# Buck_5-12V.net
KiCad netlist of a schematic drawn in Altium Designer
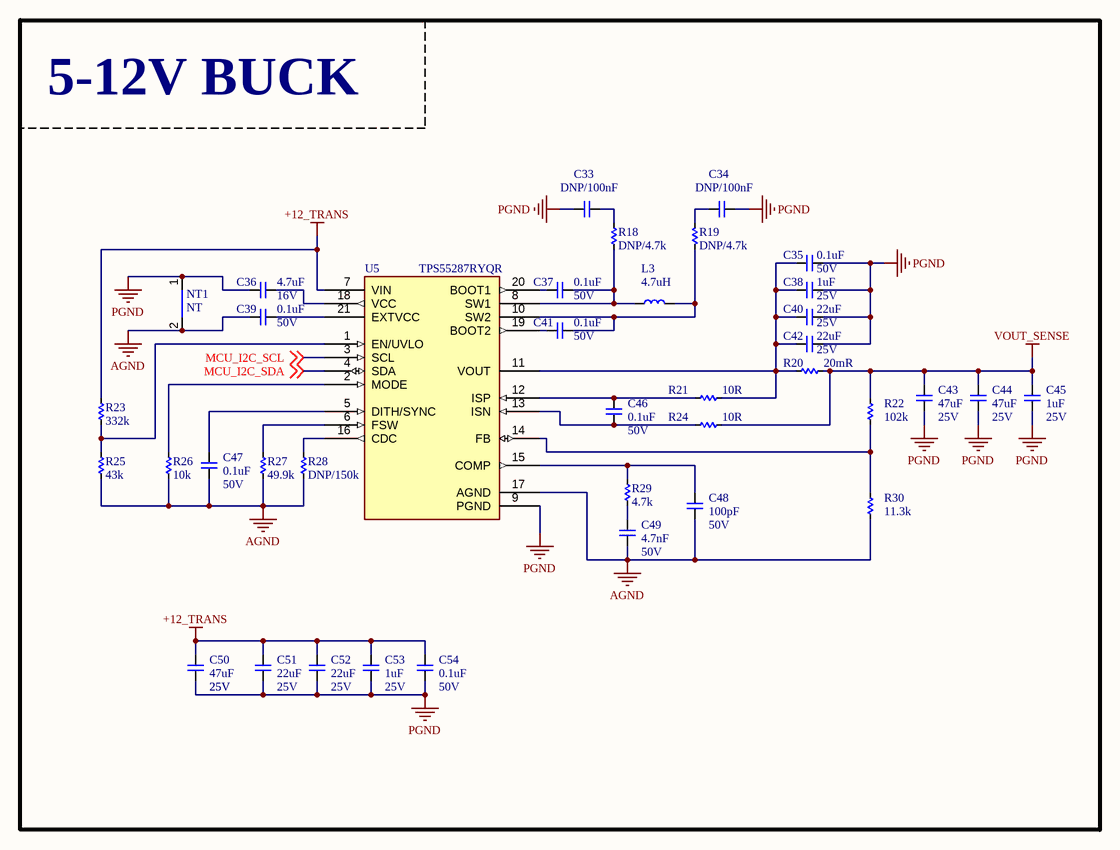
[diagram p0: Buck 5-12V.SchDoc]

(export (version "E")
  (design (tool "Eeschema 10.0.6"))
  (components
    (comp (ref "C33")
      (value "DNP/100nF")
      (footprint "CAP_C_2012X110")
      (description "CAP")
      (libsource (lib "LABLIB") (part "_CAP_C_2"))
    )
    (comp (ref "C34")
      (value "DNP/100nF")
      (footprint "CAP_C_2012X110")
      (description "CAP")
      (libsource (lib "LABLIB") (part "_CAP_C_2"))
    )
    (comp (ref "C35")
      (value "0.1uF")
      (footprint "CAP_C_1608X80")
      (description "CAP")
      (fields (field (name "VOLTAGE") "50V"))
      (libsource (lib "LABLIB") (part "_CAP_C_2"))
    )
    (comp (ref "C36")
      (value "4.7uF")
      (footprint "CAP_C_1608X80")
      (description "CAP")
      (fields (field (name "VOLTAGE") "16V"))
      (libsource (lib "LABLIB") (part "_CAP_C_2"))
    )
    (comp (ref "C37")
      (value "0.1uF")
      (footprint "CAP_C_1608X80")
      (description "CAP")
      (fields (field (name "VOLTAGE") "50V"))
      (libsource (lib "LABLIB") (part "_CAP_C_2"))
    )
    (comp (ref "C38")
      (value "1uF")
      (footprint "CAP_C_1608X80")
      (description "CAP")
      (fields (field (name "VOLTAGE") "25V"))
      (libsource (lib "LABLIB") (part "_CAP_C_2"))
    )
    (comp (ref "C39")
      (value "0.1uF")
      (footprint "CAP_C_1608X80")
      (description "CAP")
      (fields (field (name "VOLTAGE") "50V"))
      (libsource (lib "LABLIB") (part "_CAP_C_2"))
    )
    (comp (ref "C40")
      (value "22uF")
      (footprint "CAP_C_2012X110")
      (description "CAP")
      (fields (field (name "VOLTAGE") "25V"))
      (libsource (lib "LABLIB") (part "_CAP_C_2"))
    )
    (comp (ref "C41")
      (value "0.1uF")
      (footprint "CAP_C_1608X80")
      (description "CAP")
      (fields (field (name "VOLTAGE") "50V"))
      (libsource (lib "LABLIB") (part "_CAP_C_2"))
    )
    (comp (ref "C42")
      (value "22uF")
      (footprint "CAP_C_2012X110")
      (description "CAP")
      (fields (field (name "VOLTAGE") "25V"))
      (libsource (lib "LABLIB") (part "_CAP_C_2"))
    )
    (comp (ref "C43")
      (value "47uF")
      (footprint "CAP_C_3225X80")
      (description "CAP")
      (fields (field (name "VOLTAGE") "25V"))
      (libsource (lib "LABLIB") (part "_CAP_C_2"))
    )
    (comp (ref "C44")
      (value "47uF")
      (footprint "CAP_C_3225X80")
      (description "CAP")
      (fields (field (name "VOLTAGE") "25V"))
      (libsource (lib "LABLIB") (part "_CAP_C_2"))
    )
    (comp (ref "C45")
      (value "1uF")
      (footprint "CAP_C_1608X80")
      (description "CAP")
      (fields (field (name "VOLTAGE") "25V"))
      (libsource (lib "LABLIB") (part "_CAP_C_2"))
    )
    (comp (ref "C46")
      (value "0.1uF")
      (footprint "CAP_C_1608X80")
      (description "CAP")
      (fields (field (name "VOLTAGE") "50V"))
      (libsource (lib "LABLIB") (part "_CAP_C_2"))
    )
    (comp (ref "C47")
      (value "0.1uF")
      (footprint "CAP_C_1608X80")
      (description "CAP")
      (fields (field (name "VOLTAGE") "50V"))
      (libsource (lib "LABLIB") (part "_CAP_C_2"))
    )
    (comp (ref "C48")
      (value "100pF")
      (footprint "CAP_C_1608X80")
      (description "CAP")
      (fields (field (name "VOLTAGE") "50V"))
      (libsource (lib "LABLIB") (part "_CAP_C_2"))
    )
    (comp (ref "C49")
      (value "4.7nF")
      (footprint "CAP_C_1608X80")
      (description "CAP")
      (fields (field (name "VOLTAGE") "50V"))
      (libsource (lib "LABLIB") (part "_CAP_C_2"))
    )
    (comp (ref "C50")
      (value "47uF")
      (footprint "CAP_C_3225X80")
      (description "CAP")
      (fields (field (name "VOLTAGE") "25V"))
      (libsource (lib "LABLIB") (part "_CAP_C_2"))
    )
    (comp (ref "C51")
      (value "22uF")
      (footprint "CAP_C_2012X110")
      (description "CAP")
      (fields (field (name "VOLTAGE") "25V"))
      (libsource (lib "LABLIB") (part "_CAP_C_2"))
    )
    (comp (ref "C52")
      (value "22uF")
      (footprint "CAP_C_2012X110")
      (description "CAP")
      (fields (field (name "VOLTAGE") "25V"))
      (libsource (lib "LABLIB") (part "_CAP_C_2"))
    )
    (comp (ref "C53")
      (value "1uF")
      (footprint "CAP_C_1608X80")
      (description "CAP")
      (fields (field (name "VOLTAGE") "25V"))
      (libsource (lib "LABLIB") (part "_CAP_C_2"))
    )
    (comp (ref "C54")
      (value "0.1uF")
      (footprint "CAP_C_1608X80")
      (description "CAP")
      (fields (field (name "VOLTAGE") "50V"))
      (libsource (lib "LABLIB") (part "_CAP_C_2"))
    )
    (comp (ref "L3")
      (value "4.7uH")
      (footprint "Inductor SMD 6x5.7x5")
      (description "Inductor")
      (libsource (lib "chipfc_libs") (part "Inductor"))
    )
    (comp (ref "NT1")
      (value "NT")
      (footprint "NETTIE_SMD")
      (description "Net Tie SMD")
      (libsource (lib "KIENASIY123_LIB") (part "NetTie_SMD"))
    )
    (comp (ref "R18")
      (value "DNP/4.7k")
      (footprint "RES_C_3216X70")
      (description "RES")
      (libsource (lib "LABLIB") (part "_RES_B_2_2"))
    )
    (comp (ref "R19")
      (value "DNP/4.7k")
      (footprint "RES_C_3216X70")
      (description "RES")
      (libsource (lib "LABLIB") (part "_RES_B_2_2"))
    )
    (comp (ref "R20")
      (value "20mR")
      (footprint "RES_C_3216X70")
      (description "RES")
      (libsource (lib "LABLIB") (part "_RES_B_2_2"))
    )
    (comp (ref "R21")
      (value "10R")
      (footprint "RES_C_1608X60")
      (description "RES")
      (libsource (lib "LABLIB") (part "_RES_B_2_2"))
    )
    (comp (ref "R22")
      (value "102k")
      (footprint "RES_C_1608X60")
      (description "RES")
      (libsource (lib "LABLIB") (part "_RES_B_2_2"))
    )
    (comp (ref "R23")
      (value "332k")
      (footprint "RES_C_1608X60")
      (description "RES")
      (libsource (lib "LABLIB") (part "_RES_B_2_2"))
    )
    (comp (ref "R24")
      (value "10R")
      (footprint "RES_C_1608X60")
      (description "RES")
      (libsource (lib "LABLIB") (part "_RES_B_2_2"))
    )
    (comp (ref "R25")
      (value "43k")
      (footprint "RES_C_1608X60")
      (description "RES")
      (libsource (lib "LABLIB") (part "_RES_B_2_2"))
    )
    (comp (ref "R26")
      (value "10k")
      (footprint "RES_C_1608X60")
      (description "RES")
      (libsource (lib "LABLIB") (part "_RES_B_2_2"))
    )
    (comp (ref "R27")
      (value "49.9k")
      (footprint "RES_C_1608X60")
      (description "RES")
      (libsource (lib "LABLIB") (part "_RES_B_2_2"))
    )
    (comp (ref "R28")
      (value "DNP/150k")
      (footprint "RES_C_1608X60")
      (description "RES")
      (libsource (lib "LABLIB") (part "_RES_B_2_2"))
    )
    (comp (ref "R29")
      (value "4.7k")
      (footprint "RES_C_1608X60")
      (description "RES")
      (libsource (lib "LABLIB") (part "_RES_B_2_2"))
    )
    (comp (ref "R30")
      (value "11.3k")
      (footprint "RES_C_1608X60")
      (description "RES")
      (libsource (lib "LABLIB") (part "_RES_B_2_2"))
    )
    (comp (ref "U5")
      (value "TPS55287RYQR")
      (footprint "VQFN_TPS")
      (libsource (lib "KIENASIY123_LIB") (part "TPS55289-Q1"))
    )
  )
  (nets
    (net (code "1") (name "+12_TRANS") (class "Default")
      (node (ref "C50") (pin "2") (pinfunction "2_2") (pintype "passive"))
      (node (ref "C51") (pin "2") (pinfunction "2_2") (pintype "passive"))
      (node (ref "C52") (pin "2") (pinfunction "2_2") (pintype "passive"))
      (node (ref "C53") (pin "2") (pinfunction "2_2") (pintype "passive"))
      (node (ref "C54") (pin "2") (pinfunction "2_2") (pintype "passive"))
      (node (ref "R23") (pin "2") (pinfunction "2_2") (pintype "passive"))
      (node (ref "U5") (pin "7") (pinfunction "VIN_7") (pintype "power_in"))
    )
    (net (code "2") (name "AGND") (class "Default")
      (node (ref "C39") (pin "1") (pinfunction "1_1") (pintype "passive"))
      (node (ref "C47") (pin "1") (pinfunction "1_1") (pintype "passive"))
      (node (ref "C48") (pin "1") (pinfunction "1_1") (pintype "passive"))
      (node (ref "C49") (pin "1") (pinfunction "1_1") (pintype "passive"))
      (node (ref "NT1") (pin "2") (pinfunction "2_2") (pintype "passive"))
      (node (ref "R25") (pin "2") (pinfunction "2_2") (pintype "passive"))
      (node (ref "R26") (pin "1") (pinfunction "1_1") (pintype "passive"))
      (node (ref "R27") (pin "1") (pinfunction "1_1") (pintype "passive"))
      (node (ref "R28") (pin "1") (pinfunction "1_1") (pintype "passive"))
      (node (ref "R30") (pin "1") (pinfunction "1_1") (pintype "passive"))
      (node (ref "U5") (pin "17") (pinfunction "AGND_17") (pintype "power_in"))
    )
    (net (code "3") (name "MCU_I2C_SCL") (class "Default")
      (node (ref "U5") (pin "3") (pinfunction "SCL_3") (pintype "input"))
    )
    (net (code "4") (name "MCU_I2C_SDA") (class "Default")
      (node (ref "U5") (pin "4") (pinfunction "SDA_4") (pintype "bidirectional"))
    )
    (net (code "5") (name "Net-(C33-Pad1)") (class "Default")
      (node (ref "C33") (pin "1") (pinfunction "1_1") (pintype "passive"))
      (node (ref "R18") (pin "1") (pinfunction "1_1") (pintype "passive"))
    )
    (net (code "6") (name "Net-(C34-Pad1)") (class "Default")
      (node (ref "C34") (pin "1") (pinfunction "1_1") (pintype "passive"))
      (node (ref "R19") (pin "2") (pinfunction "2_2") (pintype "passive"))
    )
    (net (code "7") (name "Net-(C49-Pad2)") (class "Default")
      (node (ref "C49") (pin "2") (pinfunction "2_2") (pintype "passive"))
      (node (ref "R29") (pin "1") (pinfunction "1_1") (pintype "passive"))
    )
    (net (code "8") (name "Net-(U5-BOOT1)") (class "Default")
      (node (ref "C37") (pin "2") (pinfunction "2_2") (pintype "passive"))
      (node (ref "U5") (pin "20") (pinfunction "BOOT1_20") (pintype "output"))
    )
    (net (code "9") (name "Net-(U5-BOOT2)") (class "Default")
      (node (ref "C41") (pin "2") (pinfunction "2_2") (pintype "passive"))
      (node (ref "U5") (pin "19") (pinfunction "BOOT2_19") (pintype "output"))
    )
    (net (code "10") (name "Net-(U5-CDC)") (class "Default")
      (node (ref "R28") (pin "2") (pinfunction "2_2") (pintype "passive"))
      (node (ref "U5") (pin "16") (pinfunction "CDC_16") (pintype "output"))
    )
    (net (code "11") (name "Net-(U5-COMP)") (class "Default")
      (node (ref "C48") (pin "2") (pinfunction "2_2") (pintype "passive"))
      (node (ref "R29") (pin "2") (pinfunction "2_2") (pintype "passive"))
      (node (ref "U5") (pin "15") (pinfunction "COMP_15") (pintype "output"))
    )
    (net (code "12") (name "Net-(U5-DITH{slash}SYNC)") (class "Default")
      (node (ref "C47") (pin "2") (pinfunction "2_2") (pintype "passive"))
      (node (ref "U5") (pin "5") (pinfunction "DITH/SYNC_5") (pintype "input"))
    )
    (net (code "13") (name "Net-(U5-EN{slash}UVLO)") (class "Default")
      (node (ref "R23") (pin "1") (pinfunction "1_1") (pintype "passive"))
      (node (ref "R25") (pin "1") (pinfunction "1_1") (pintype "passive"))
      (node (ref "U5") (pin "1") (pinfunction "EN/UVLO_1") (pintype "input"))
    )
    (net (code "14") (name "Net-(U5-EXTVCC)") (class "Default")
      (node (ref "C39") (pin "2") (pinfunction "2_2") (pintype "passive"))
      (node (ref "U5") (pin "21") (pinfunction "EXTVCC_21") (pintype "power_in"))
    )
    (net (code "15") (name "Net-(U5-FB)") (class "Default")
      (node (ref "R22") (pin "1") (pinfunction "1_1") (pintype "passive"))
      (node (ref "R30") (pin "2") (pinfunction "2_2") (pintype "passive"))
      (node (ref "U5") (pin "14") (pinfunction "FB_14") (pintype "bidirectional"))
    )
    (net (code "16") (name "Net-(U5-FSW)") (class "Default")
      (node (ref "R27") (pin "2") (pinfunction "2_2") (pintype "passive"))
      (node (ref "U5") (pin "6") (pinfunction "FSW_6") (pintype "input"))
    )
    (net (code "17") (name "Net-(U5-ISN)") (class "Default")
      (node (ref "C46") (pin "2") (pinfunction "2_2") (pintype "passive"))
      (node (ref "R24") (pin "2") (pinfunction "2_2") (pintype "passive"))
      (node (ref "U5") (pin "13") (pinfunction "ISN_13") (pintype "input"))
    )
    (net (code "18") (name "Net-(U5-ISP)") (class "Default")
      (node (ref "C46") (pin "1") (pinfunction "1_1") (pintype "passive"))
      (node (ref "R21") (pin "2") (pinfunction "2_2") (pintype "passive"))
      (node (ref "U5") (pin "12") (pinfunction "ISP_12") (pintype "input"))
    )
    (net (code "19") (name "Net-(U5-MODE)") (class "Default")
      (node (ref "R26") (pin "2") (pinfunction "2_2") (pintype "passive"))
      (node (ref "U5") (pin "2") (pinfunction "MODE_2") (pintype "input"))
    )
    (net (code "20") (name "Net-(U5-SW1)") (class "Default")
      (node (ref "C37") (pin "1") (pinfunction "1_1") (pintype "passive"))
      (node (ref "L3") (pin "1") (pinfunction "1_1") (pintype "passive"))
      (node (ref "R18") (pin "2") (pinfunction "2_2") (pintype "passive"))
      (node (ref "U5") (pin "8") (pinfunction "SW1_8") (pintype "power_in"))
    )
    (net (code "21") (name "Net-(U5-SW2)") (class "Default")
      (node (ref "C41") (pin "1") (pinfunction "1_1") (pintype "passive"))
      (node (ref "L3") (pin "2") (pinfunction "2_2") (pintype "passive"))
      (node (ref "R19") (pin "1") (pinfunction "1_1") (pintype "passive"))
      (node (ref "U5") (pin "10") (pinfunction "SW2_10") (pintype "power_in"))
    )
    (net (code "22") (name "Net-(U5-VCC)") (class "Default")
      (node (ref "C36") (pin "2") (pinfunction "2_2") (pintype "passive"))
      (node (ref "U5") (pin "18") (pinfunction "VCC_18") (pintype "output"))
    )
    (net (code "23") (name "Net-(U5-VOUT)") (class "Default")
      (node (ref "C35") (pin "2") (pinfunction "2_2") (pintype "passive"))
      (node (ref "C38") (pin "2") (pinfunction "2_2") (pintype "passive"))
      (node (ref "C40") (pin "2") (pinfunction "2_2") (pintype "passive"))
      (node (ref "C42") (pin "2") (pinfunction "2_2") (pintype "passive"))
      (node (ref "R20") (pin "2") (pinfunction "2_2") (pintype "passive"))
      (node (ref "R21") (pin "1") (pinfunction "1_1") (pintype "passive"))
      (node (ref "U5") (pin "11") (pinfunction "VOUT_11") (pintype "power_in"))
    )
    (net (code "24") (name "PGND") (class "Default")
      (node (ref "C33") (pin "2") (pinfunction "2_2") (pintype "passive"))
      (node (ref "C34") (pin "2") (pinfunction "2_2") (pintype "passive"))
      (node (ref "C35") (pin "1") (pinfunction "1_1") (pintype "passive"))
      (node (ref "C36") (pin "1") (pinfunction "1_1") (pintype "passive"))
      (node (ref "C38") (pin "1") (pinfunction "1_1") (pintype "passive"))
      (node (ref "C40") (pin "1") (pinfunction "1_1") (pintype "passive"))
      (node (ref "C42") (pin "1") (pinfunction "1_1") (pintype "passive"))
      (node (ref "C43") (pin "1") (pinfunction "1_1") (pintype "passive"))
      (node (ref "C44") (pin "1") (pinfunction "1_1") (pintype "passive"))
      (node (ref "C45") (pin "1") (pinfunction "1_1") (pintype "passive"))
      (node (ref "C50") (pin "1") (pinfunction "1_1") (pintype "passive"))
      (node (ref "C51") (pin "1") (pinfunction "1_1") (pintype "passive"))
      (node (ref "C52") (pin "1") (pinfunction "1_1") (pintype "passive"))
      (node (ref "C53") (pin "1") (pinfunction "1_1") (pintype "passive"))
      (node (ref "C54") (pin "1") (pinfunction "1_1") (pintype "passive"))
      (node (ref "NT1") (pin "1") (pinfunction "1_1") (pintype "passive"))
      (node (ref "U5") (pin "9") (pinfunction "PGND_9") (pintype "power_in"))
    )
    (net (code "25") (name "VOUT_SENSE") (class "Default")
      (node (ref "C43") (pin "2") (pinfunction "2_2") (pintype "passive"))
      (node (ref "C44") (pin "2") (pinfunction "2_2") (pintype "passive"))
      (node (ref "C45") (pin "2") (pinfunction "2_2") (pintype "passive"))
      (node (ref "R20") (pin "1") (pinfunction "1_1") (pintype "passive"))
      (node (ref "R22") (pin "2") (pinfunction "2_2") (pintype "passive"))
      (node (ref "R24") (pin "1") (pinfunction "1_1") (pintype "passive"))
    )
  )
)
